# synth_r0_1.net
KiCad netlist of a schematic drawn in EAGLE
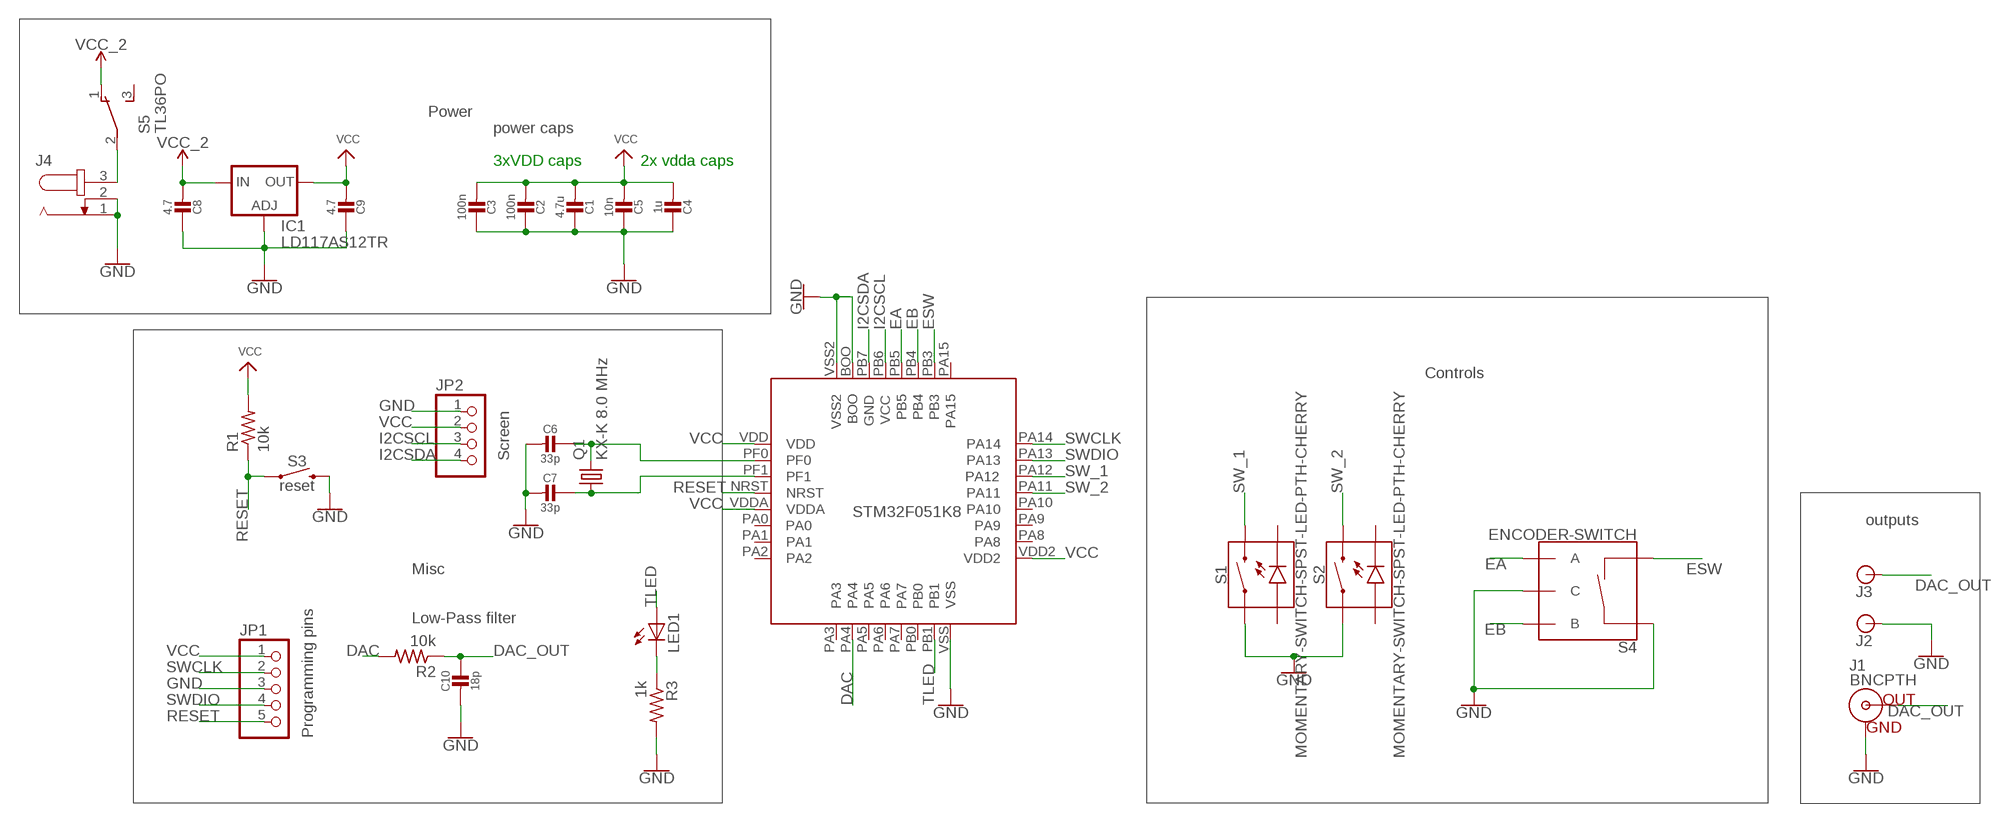
[diagram p0: schematic, sheet 1]

(export (version "E")
  (design (tool "Eeschema 10.0.6"))
  (components
    (comp (ref "C1")
      (value "4.7u")
      (footprint "eagle-import:0805-NO")
      (libsource (lib "eagle-import") (part "CAP_CERAMIC0805-NOOUTLINE"))
    )
    (comp (ref "C2")
      (value "100n")
      (footprint "eagle-import:0805-NO")
      (libsource (lib "eagle-import") (part "CAP_CERAMIC0805-NOOUTLINE"))
    )
    (comp (ref "C3")
      (value "100n")
      (footprint "eagle-import:0805-NO")
      (libsource (lib "eagle-import") (part "CAP_CERAMIC0805-NOOUTLINE"))
    )
    (comp (ref "C4")
      (value "1u")
      (footprint "eagle-import:0805-NO")
      (libsource (lib "eagle-import") (part "CAP_CERAMIC0805-NOOUTLINE"))
    )
    (comp (ref "C5")
      (value "10n")
      (footprint "eagle-import:0805-NO")
      (libsource (lib "eagle-import") (part "CAP_CERAMIC0805-NOOUTLINE"))
    )
    (comp (ref "C6")
      (value "33p")
      (footprint "eagle-import:0805-NO")
      (libsource (lib "eagle-import") (part "CAP_CERAMIC0805-NOOUTLINE"))
    )
    (comp (ref "C7")
      (value "33p")
      (footprint "eagle-import:0805-NO")
      (libsource (lib "eagle-import") (part "CAP_CERAMIC0805-NOOUTLINE"))
    )
    (comp (ref "C8")
      (value "4.7")
      (footprint "eagle-import:0805-NO")
      (libsource (lib "eagle-import") (part "CAP_CERAMIC0805-NOOUTLINE"))
    )
    (comp (ref "C9")
      (value "4.7")
      (footprint "eagle-import:0805-NO")
      (libsource (lib "eagle-import") (part "CAP_CERAMIC0805-NOOUTLINE"))
    )
    (comp (ref "C10")
      (value "18p")
      (footprint "eagle-import:0805-NO")
      (libsource (lib "eagle-import") (part "CAP_CERAMIC0805-NOOUTLINE"))
    )
    (comp (ref "IC1")
      (value "LD117AS12TR")
      (footprint "eagle-import:SOT223")
      (libsource (lib "eagle-import") (part "LD117A?S12TR"))
    )
    (comp (ref "J1")
      (value "BNCPTH")
      (footprint "eagle-import:BNC")
      (libsource (lib "eagle-import") (part "BNCPTH"))
    )
    (comp (ref "J2")
      (value "BANANA_CONN")
      (footprint "eagle-import:BANANA_CONN")
      (libsource (lib "eagle-import") (part "BANANA_CONN"))
    )
    (comp (ref "J3")
      (value "BANANA_CONN")
      (footprint "eagle-import:BANANA_CONN")
      (libsource (lib "eagle-import") (part "BANANA_CONN"))
    )
    (comp (ref "J4")
      (value "JACK-PLUG1")
      (footprint "eagle-import:SPC4078")
      (libsource (lib "eagle-import") (part "JACK-PLUG1"))
    )
    (comp (ref "JP1")
      (value "PINHD-1X5")
      (footprint "eagle-import:1X05")
      (libsource (lib "eagle-import") (part "PINHD-1X5"))
    )
    (comp (ref "JP2")
      (value "PINHD-1X4")
      (footprint "eagle-import:1X04")
      (libsource (lib "eagle-import") (part "PINHD-1X4"))
    )
    (comp (ref "LED1")
      (value "LEDCHIPLED_0805")
      (footprint "eagle-import:CHIPLED_0805")
      (libsource (lib "eagle-import") (part "LEDCHIPLED_0805"))
    )
    (comp (ref "Q1")
      (value "KX-K 8.0 MHz")
      (footprint "eagle-import:HC49_S")
      (libsource (lib "eagle-import") (part "CRYSTALHC49S"))
    )
    (comp (ref "R1")
      (value "10k")
      (footprint "eagle-import:R0805")
      (libsource (lib "eagle-import") (part "R-US_R0805"))
    )
    (comp (ref "R2")
      (value "10k")
      (footprint "eagle-import:R0805")
      (libsource (lib "eagle-import") (part "R-US_R0805"))
    )
    (comp (ref "R3")
      (value "1k")
      (footprint "eagle-import:R0805")
      (libsource (lib "eagle-import") (part "R-US_R0805"))
    )
    (comp (ref "S1")
      (value "MOMENTARY-SWITCH-SPST-LED-PTH-CHERRY")
      (footprint "eagle-import:CHERRY-MX-LED")
      (libsource (lib "eagle-import") (part "MOMENTARY-SWITCH-SPST-LED-PTH-CHERRY"))
    )
    (comp (ref "S2")
      (value "MOMENTARY-SWITCH-SPST-LED-PTH-CHERRY")
      (footprint "eagle-import:CHERRY-MX-LED")
      (libsource (lib "eagle-import") (part "MOMENTARY-SWITCH-SPST-LED-PTH-CHERRY"))
    )
    (comp (ref "S3")
      (value "reset")
      (footprint "eagle-import:TACTILE_SWITCH_SMD_5.2MM")
      (libsource (lib "eagle-import") (part "MOMENTARY-SWITCH-SPST-SMD-5.2-REDUNDANT"))
    )
    (comp (ref "S4")
      (value "ENCODER-SWITCH")
      (footprint "eagle-import:ROTARY_ENC_PLAIN")
      (libsource (lib "eagle-import") (part "ENCODER-SWITCH"))
    )
    (comp (ref "S5")
      (value "TL36PO")
      (footprint "eagle-import:TL3XPO")
      (libsource (lib "eagle-import") (part "TL36PO"))
    )
    (comp (ref "U$1")
      (value "STM32F051K8")
      (footprint "eagle-import:LQFP32-7X7")
      (libsource (lib "eagle-import") (part "STM32F051K8"))
    )
  )
  (nets
    (net (code "1") (name "/DAC") (class "Default")
      (node (ref "R2") (pin "2") (pinfunction "2_2") (pintype "passive"))
      (node (ref "U$1") (pin "PA4") (pinfunction "PA4_PA4") (pintype "bidirectional"))
    )
    (net (code "2") (name "/DAC_OUT") (class "Default")
      (node (ref "C10") (pin "1") (pinfunction "1_1") (pintype "passive"))
      (node (ref "J1") (pin "S") (pinfunction "OUT_S") (pintype "bidirectional"))
      (node (ref "J3") (pin "P$1") (pinfunction "1_P$1") (pintype "passive"))
      (node (ref "R2") (pin "1") (pinfunction "1_1") (pintype "passive"))
    )
    (net (code "3") (name "/EA") (class "Default")
      (node (ref "S4") (pin "A") (pinfunction "A_A") (pintype "bidirectional"))
      (node (ref "U$1") (pin "PB5") (pinfunction "PB5_PB5") (pintype "bidirectional"))
    )
    (net (code "4") (name "/EB") (class "Default")
      (node (ref "S4") (pin "B") (pinfunction "B_B") (pintype "bidirectional"))
      (node (ref "U$1") (pin "PB4") (pinfunction "PB4_PB4") (pintype "bidirectional"))
    )
    (net (code "5") (name "/ESW") (class "Default")
      (node (ref "S4") (pin "SW-") (pinfunction "SW-_SW-") (pintype "bidirectional"))
      (node (ref "U$1") (pin "PB3") (pinfunction "PB3_PB3") (pintype "bidirectional"))
    )
    (net (code "6") (name "/I2CSCL") (class "Default")
      (node (ref "JP2") (pin "3") (pinfunction "3_3") (pintype "passive"))
      (node (ref "U$1") (pin "PB6") (pinfunction "PB6_PB6") (pintype "power_in"))
    )
    (net (code "7") (name "/I2CSDA") (class "Default")
      (node (ref "JP2") (pin "4") (pinfunction "4_4") (pintype "passive"))
      (node (ref "U$1") (pin "PB7") (pinfunction "PB7_PB7") (pintype "power_in"))
    )
    (net (code "8") (name "/PA0") (class "Default")
      (node (ref "U$1") (pin "PA0") (pinfunction "PA0_PA0") (pintype "power_in"))
    )
    (net (code "9") (name "/PA7") (class "Default")
      (node (ref "U$1") (pin "PA7") (pinfunction "PA7_PA7") (pintype "power_in"))
    )
    (net (code "10") (name "/PB0") (class "Default")
      (node (ref "U$1") (pin "PB0") (pinfunction "PB0_PB0") (pintype "power_in"))
    )
    (net (code "11") (name "/RESET") (class "Default")
      (node (ref "JP1") (pin "5") (pinfunction "5_5") (pintype "passive"))
      (node (ref "R1") (pin "1") (pinfunction "1_1") (pintype "passive"))
      (node (ref "S3") (pin "1") (pinfunction "1_1") (pintype "passive"))
      (node (ref "S3") (pin "2") (pinfunction "1_2") (pintype "passive"))
      (node (ref "U$1") (pin "NRST") (pinfunction "NRST_NRST") (pintype "input"))
    )
    (net (code "12") (name "/SWCLK") (class "Default")
      (node (ref "JP1") (pin "2") (pinfunction "2_2") (pintype "passive"))
      (node (ref "U$1") (pin "PA14") (pinfunction "PA14_PA14") (pintype "bidirectional"))
    )
    (net (code "13") (name "/SWDIO") (class "Default")
      (node (ref "JP1") (pin "4") (pinfunction "4_4") (pintype "passive"))
      (node (ref "U$1") (pin "PA13") (pinfunction "PA13_PA13") (pintype "output"))
    )
    (net (code "14") (name "/SW_1") (class "Default")
      (node (ref "S1") (pin "S2") (pinfunction "2_S2") (pintype "passive"))
      (node (ref "U$1") (pin "PA12") (pinfunction "PA12_PA12") (pintype "power_in"))
    )
    (net (code "15") (name "/SW_2") (class "Default")
      (node (ref "S2") (pin "S2") (pinfunction "2_S2") (pintype "passive"))
      (node (ref "U$1") (pin "PA11") (pinfunction "PA11_PA11") (pintype "input"))
    )
    (net (code "16") (name "/TLED") (class "Default")
      (node (ref "LED1") (pin "A") (pinfunction "A_A") (pintype "passive"))
      (node (ref "U$1") (pin "PB1") (pinfunction "PB1_PB1") (pintype "bidirectional"))
    )
    (net (code "17") (name "GND") (class "Default")
      (node (ref "C1") (pin "1") (pinfunction "1_1") (pintype "passive"))
      (node (ref "C10") (pin "2") (pinfunction "2_2") (pintype "passive"))
      (node (ref "C2") (pin "1") (pinfunction "1_1") (pintype "passive"))
      (node (ref "C3") (pin "1") (pinfunction "1_1") (pintype "passive"))
      (node (ref "C4") (pin "1") (pinfunction "1_1") (pintype "passive"))
      (node (ref "C5") (pin "1") (pinfunction "1_1") (pintype "passive"))
      (node (ref "C6") (pin "2") (pinfunction "2_2") (pintype "passive"))
      (node (ref "C7") (pin "2") (pinfunction "2_2") (pintype "passive"))
      (node (ref "C8") (pin "1") (pinfunction "1_1") (pintype "passive"))
      (node (ref "C9") (pin "1") (pinfunction "1_1") (pintype "passive"))
      (node (ref "IC1") (pin "1") (pinfunction "ADJ_1") (pintype "input"))
      (node (ref "J1") (pin "GND") (pinfunction "GND_GND") (pintype "bidirectional"))
      (node (ref "J2") (pin "P$1") (pinfunction "1_P$1") (pintype "passive"))
      (node (ref "J4") (pin "1") (pinfunction "1_1") (pintype "passive"))
      (node (ref "J4") (pin "2") (pinfunction "2_2") (pintype "passive"))
      (node (ref "JP1") (pin "3") (pinfunction "3_3") (pintype "passive"))
      (node (ref "JP2") (pin "1") (pinfunction "1_1") (pintype "passive"))
      (node (ref "R3") (pin "2") (pinfunction "2_2") (pintype "passive"))
      (node (ref "S1") (pin "S1") (pinfunction "1_S1") (pintype "passive"))
      (node (ref "S2") (pin "S1") (pinfunction "1_S1") (pintype "passive"))
      (node (ref "S3") (pin "3") (pinfunction "2_3") (pintype "passive"))
      (node (ref "S3") (pin "4") (pinfunction "2_4") (pintype "passive"))
      (node (ref "S4") (pin "C") (pinfunction "C_C") (pintype "bidirectional"))
      (node (ref "S4") (pin "SW+") (pinfunction "SW+_SW+") (pintype "bidirectional"))
      (node (ref "U$1") (pin "BOO") (pinfunction "BOO_BOO") (pintype "bidirectional"))
      (node (ref "U$1") (pin "VSS") (pinfunction "VSS_VSS") (pintype "bidirectional"))
      (node (ref "U$1") (pin "VSS2") (pinfunction "VSS2_VSS2") (pintype "bidirectional"))
    )
    (net (code "18") (name "Net-(C6-Pad1)") (class "Default")
      (node (ref "C6") (pin "1") (pinfunction "1_1") (pintype "passive"))
      (node (ref "Q1") (pin "2") (pinfunction "2_2") (pintype "passive"))
      (node (ref "U$1") (pin "PF0") (pinfunction "PF0_PF0") (pintype "bidirectional"))
    )
    (net (code "19") (name "Net-(C7-Pad1)") (class "Default")
      (node (ref "C7") (pin "1") (pinfunction "1_1") (pintype "passive"))
      (node (ref "Q1") (pin "1") (pinfunction "1_1") (pintype "passive"))
      (node (ref "U$1") (pin "PF1") (pinfunction "PF1_PF1") (pintype "bidirectional"))
    )
    (net (code "20") (name "Net-(LED1-PadC)") (class "Default")
      (node (ref "LED1") (pin "C") (pinfunction "C_C") (pintype "passive"))
      (node (ref "R3") (pin "1") (pinfunction "1_1") (pintype "passive"))
    )
    (net (code "21") (name "Net-(S5-P)") (class "Default")
      (node (ref "J4") (pin "3") (pinfunction "3_3") (pintype "passive"))
      (node (ref "S5") (pin "2") (pinfunction "P_2") (pintype "passive"))
    )
    (net (code "22") (name "VCC") (class "Default")
      (node (ref "C1") (pin "2") (pinfunction "2_2") (pintype "passive"))
      (node (ref "C2") (pin "2") (pinfunction "2_2") (pintype "passive"))
      (node (ref "C3") (pin "2") (pinfunction "2_2") (pintype "passive"))
      (node (ref "C4") (pin "2") (pinfunction "2_2") (pintype "passive"))
      (node (ref "C5") (pin "2") (pinfunction "2_2") (pintype "passive"))
      (node (ref "C9") (pin "2") (pinfunction "2_2") (pintype "passive"))
      (node (ref "IC1") (pin "4") (pinfunction "OUT_4") (pintype "passive"))
      (node (ref "JP1") (pin "1") (pinfunction "1_1") (pintype "passive"))
      (node (ref "JP2") (pin "2") (pinfunction "2_2") (pintype "passive"))
      (node (ref "R1") (pin "2") (pinfunction "2_2") (pintype "passive"))
      (node (ref "U$1") (pin "VDD") (pinfunction "VDD_VDD") (pintype "bidirectional"))
      (node (ref "U$1") (pin "VDD2") (pinfunction "VDD2_VDD2") (pintype "bidirectional"))
      (node (ref "U$1") (pin "VDDA") (pinfunction "VDDA_VDDA") (pintype "input"))
    )
    (net (code "23") (name "VCC_2") (class "Default")
      (node (ref "C8") (pin "2") (pinfunction "2_2") (pintype "passive"))
      (node (ref "IC1") (pin "3") (pinfunction "IN_3") (pintype "input"))
      (node (ref "S5") (pin "1") (pinfunction "O_1") (pintype "passive"))
    )
    (net (code "24") (name "unconnected-(S1-C-PadK)") (class "Default")
      (node (ref "S1") (pin "K") (pinfunction "C_K") (pintype "passive"))
    )
    (net (code "25") (name "unconnected-(S1-PadA)") (class "Default")
      (node (ref "S1") (pin "A") (pinfunction "A_A") (pintype "passive"))
    )
    (net (code "26") (name "unconnected-(S2-C-PadK)") (class "Default")
      (node (ref "S2") (pin "K") (pinfunction "C_K") (pintype "passive"))
    )
    (net (code "27") (name "unconnected-(S2-PadA)") (class "Default")
      (node (ref "S2") (pin "A") (pinfunction "A_A") (pintype "passive"))
    )
    (net (code "28") (name "unconnected-(S5-S-Pad3)") (class "Default")
      (node (ref "S5") (pin "3") (pinfunction "S_3") (pintype "passive"))
    )
    (net (code "29") (name "unconnected-(U$1-PadPA1)") (class "Default")
      (node (ref "U$1") (pin "PA1") (pinfunction "PA1_PA1") (pintype "input"))
    )
    (net (code "30") (name "unconnected-(U$1-PadPA2)") (class "Default")
      (node (ref "U$1") (pin "PA2") (pinfunction "PA2_PA2") (pintype "bidirectional"))
    )
    (net (code "31") (name "unconnected-(U$1-PadPA3)") (class "Default")
      (node (ref "U$1") (pin "PA3") (pinfunction "PA3_PA3") (pintype "bidirectional"))
    )
    (net (code "32") (name "unconnected-(U$1-PadPA5)") (class "Default")
      (node (ref "U$1") (pin "PA5") (pinfunction "PA5_PA5") (pintype "bidirectional"))
    )
    (net (code "33") (name "unconnected-(U$1-PadPA6)") (class "Default")
      (node (ref "U$1") (pin "PA6") (pinfunction "PA6_PA6") (pintype "bidirectional"))
    )
    (net (code "34") (name "unconnected-(U$1-PadPA8)") (class "Default")
      (node (ref "U$1") (pin "PA8") (pinfunction "PA8_PA8") (pintype "bidirectional"))
    )
    (net (code "35") (name "unconnected-(U$1-PadPA9)") (class "Default")
      (node (ref "U$1") (pin "PA9") (pinfunction "PA9_PA9") (pintype "bidirectional"))
    )
    (net (code "36") (name "unconnected-(U$1-PadPA10)") (class "Default")
      (node (ref "U$1") (pin "PA10") (pinfunction "PA10_PA10") (pintype "input"))
    )
    (net (code "37") (name "unconnected-(U$1-PadPA15)") (class "Default")
      (node (ref "U$1") (pin "PA15") (pinfunction "PA15_PA15") (pintype "bidirectional"))
    )
  )
)
